# TimePassThrough.net
KiCad netlist of a schematic drawn in EAGLE
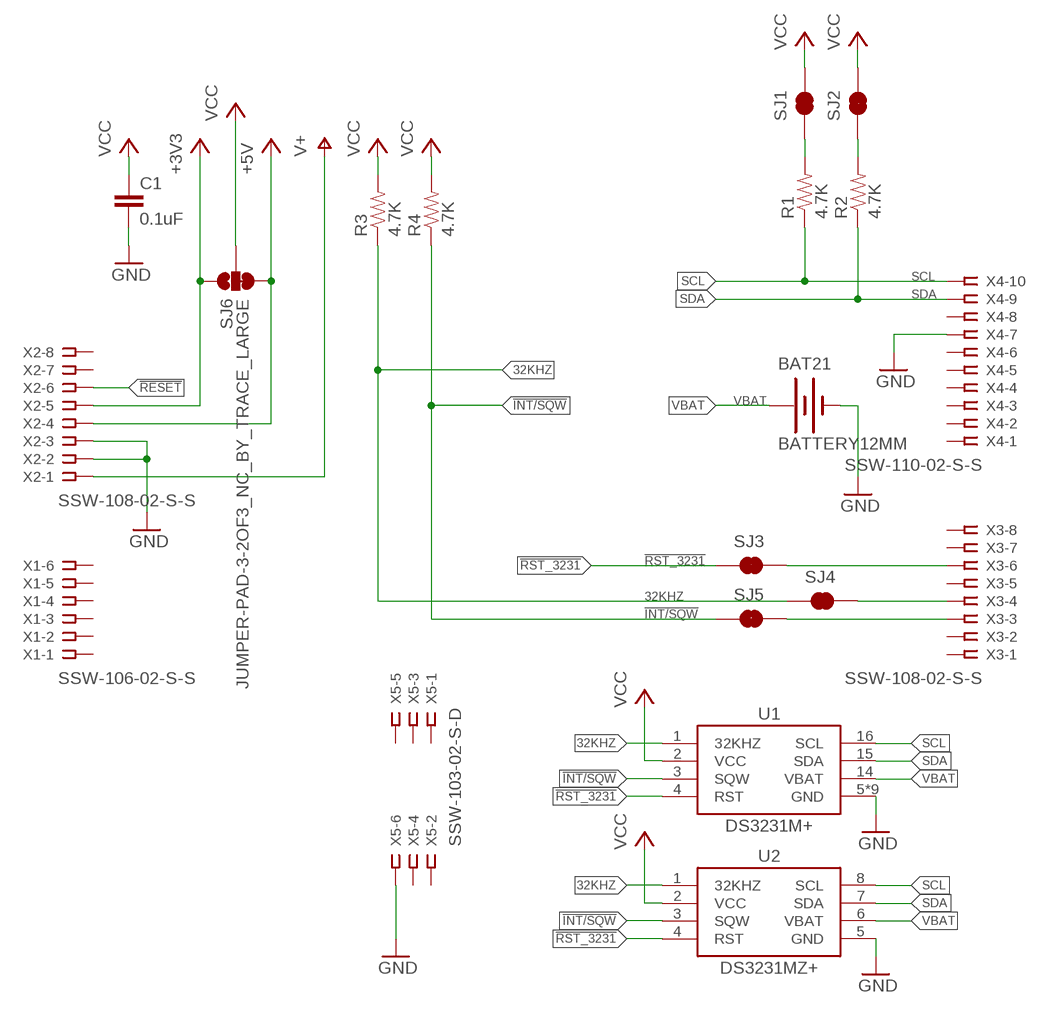
[diagram p0: schematic, sheet 1]

(export (version "E")
  (design (tool "Eeschema 10.0.6"))
  (components
    (comp (ref "BAT21")
      (value "BATTERY12MM")
      (footprint "eagle-import:BATTCON_12MM")
      (libsource (lib "eagle-import") (part "BATTERY12MM"))
    )
    (comp (ref "C1")
      (value "0.1uF")
      (footprint "eagle-import:0805")
      (libsource (lib "eagle-import") (part "CAP0805"))
    )
    (comp (ref "R1")
      (value "4.7K")
      (footprint "eagle-import:0805")
      (libsource (lib "eagle-import") (part "RESISTOR0805-RES"))
    )
    (comp (ref "R2")
      (value "4.7K")
      (footprint "eagle-import:0805")
      (libsource (lib "eagle-import") (part "RESISTOR0805-RES"))
    )
    (comp (ref "R3")
      (value "4.7K")
      (footprint "eagle-import:0805")
      (libsource (lib "eagle-import") (part "RESISTOR0805-RES"))
    )
    (comp (ref "R4")
      (value "4.7K")
      (footprint "eagle-import:0805")
      (libsource (lib "eagle-import") (part "RESISTOR0805-RES"))
    )
    (comp (ref "SJ1")
      (value "JUMPER-PAD-2-NC_BY_TRACE")
      (footprint "eagle-import:PAD-JUMPER-2-NC_BY_TRACE_YES_SILK")
      (libsource (lib "eagle-import") (part "JUMPER-PAD-2-NC_BY_TRACE"))
    )
    (comp (ref "SJ2")
      (value "JUMPER-PAD-2-NC_BY_TRACE")
      (footprint "eagle-import:PAD-JUMPER-2-NC_BY_TRACE_YES_SILK")
      (libsource (lib "eagle-import") (part "JUMPER-PAD-2-NC_BY_TRACE"))
    )
    (comp (ref "SJ3")
      (value "JUMPER-PAD-2-NC_BY_TRACE")
      (footprint "eagle-import:PAD-JUMPER-2-NC_BY_TRACE_YES_SILK")
      (libsource (lib "eagle-import") (part "JUMPER-PAD-2-NC_BY_TRACE"))
    )
    (comp (ref "SJ4")
      (value "JUMPER-PAD-2-NC_BY_TRACE")
      (footprint "eagle-import:PAD-JUMPER-2-NC_BY_TRACE_YES_SILK")
      (libsource (lib "eagle-import") (part "JUMPER-PAD-2-NC_BY_TRACE"))
    )
    (comp (ref "SJ5")
      (value "JUMPER-PAD-2-NC_BY_TRACE")
      (footprint "eagle-import:PAD-JUMPER-2-NC_BY_TRACE_YES_SILK")
      (libsource (lib "eagle-import") (part "JUMPER-PAD-2-NC_BY_TRACE"))
    )
    (comp (ref "SJ6")
      (value "JUMPER-PAD-3-2OF3_NC_BY_TRACE_LARGE")
      (footprint "eagle-import:PAD-JUMPER-3-2OF3_NC_BY_TRACE_YES_SILK_LARGE")
      (libsource (lib "eagle-import") (part "JUMPER-PAD-3-2OF3_NC_BY_TRACE_LARGE"))
    )
    (comp (ref "U1")
      (value "DS3231M+")
      (footprint "eagle-import:W16MK+1")
      (libsource (lib "eagle-import") (part "DS3231M+"))
    )
    (comp (ref "U2")
      (value "DS3231MZ+")
      (footprint "eagle-import:S8MK+1")
      (libsource (lib "eagle-import") (part "DS3231MZ+"))
    )
    (comp (ref "X1")
      (value "SSW-106-02-S-S")
      (footprint "eagle-import:SSW-106-02-S-S")
      (libsource (lib "eagle-import") (part "SSW-106-02-S-S"))
    )
    (comp (ref "X2")
      (value "SSW-108-02-S-S")
      (footprint "eagle-import:SSW-108-02-S-S")
      (libsource (lib "eagle-import") (part "SSW-108-02-S-S"))
    )
    (comp (ref "X3")
      (value "SSW-108-02-S-S")
      (footprint "eagle-import:SSW-108-02-S-S")
      (libsource (lib "eagle-import") (part "SSW-108-02-S-S"))
    )
    (comp (ref "X4")
      (value "SSW-110-02-S-S")
      (footprint "eagle-import:SSW-110-02-S-S")
      (libsource (lib "eagle-import") (part "SSW-110-02-S-S"))
    )
    (comp (ref "X5")
      (value "SSW-103-02-S-D")
      (footprint "eagle-import:SSW-103-02-S-D")
      (libsource (lib "eagle-import") (part "SSW-103-02-S-D"))
    )
  )
  (nets
    (net (code "1") (name "+3V3") (class "Default")
      (node (ref "SJ6") (pin "1") (pinfunction "1_1") (pintype "passive"))
      (node (ref "X2") (pin "5") (pinfunction "1_5") (pintype "passive"))
    )
    (net (code "2") (name "+5V") (class "Default")
      (node (ref "SJ6") (pin "3") (pinfunction "3_3") (pintype "passive"))
      (node (ref "X2") (pin "4") (pinfunction "1_4") (pintype "passive"))
    )
    (net (code "3") (name "/~{INT{slash}SQW}") (class "Default")
      (node (ref "R4") (pin "1") (pinfunction "1_1") (pintype "passive"))
      (node (ref "SJ5") (pin "1") (pinfunction "1_1") (pintype "passive"))
      (node (ref "U1") (pin "3") (pinfunction "SQW_3") (pintype "output"))
      (node (ref "U2") (pin "3") (pinfunction "SQW_3") (pintype "output"))
    )
    (net (code "4") (name "/~{RESET}") (class "Default")
      (node (ref "X2") (pin "6") (pinfunction "1_6") (pintype "passive"))
    )
    (net (code "5") (name "/~{RST_3231}") (class "Default")
      (node (ref "SJ3") (pin "1") (pinfunction "1_1") (pintype "passive"))
      (node (ref "U1") (pin "4") (pinfunction "RST_4") (pintype "bidirectional"))
      (node (ref "U2") (pin "4") (pinfunction "RST_4") (pintype "bidirectional"))
    )
    (net (code "6") (name "32KHZ") (class "Default")
      (node (ref "R3") (pin "1") (pinfunction "1_1") (pintype "passive"))
      (node (ref "SJ4") (pin "1") (pinfunction "1_1") (pintype "passive"))
      (node (ref "U1") (pin "1") (pinfunction "32KHZ_1") (pintype "output"))
      (node (ref "U2") (pin "1") (pinfunction "32KHZ_1") (pintype "output"))
    )
    (net (code "7") (name "GND") (class "Default")
      (node (ref "BAT21") (pin "GND") (pinfunction "-_GND") (pintype "passive"))
      (node (ref "C1") (pin "2") (pinfunction "2_2") (pintype "passive"))
      (node (ref "U1") (pin "10") (pinfunction "GND_10") (pintype "power_in"))
      (node (ref "U1") (pin "11") (pinfunction "GND_11") (pintype "power_in"))
      (node (ref "U1") (pin "12") (pinfunction "GND_12") (pintype "power_in"))
      (node (ref "U1") (pin "13") (pinfunction "GND_13") (pintype "power_in"))
      (node (ref "U1") (pin "5") (pinfunction "GND_5") (pintype "power_in"))
      (node (ref "U1") (pin "6") (pinfunction "GND_6") (pintype "power_in"))
      (node (ref "U1") (pin "7") (pinfunction "GND_7") (pintype "power_in"))
      (node (ref "U1") (pin "8") (pinfunction "GND_8") (pintype "power_in"))
      (node (ref "U1") (pin "9") (pinfunction "GND_9") (pintype "power_in"))
      (node (ref "U2") (pin "5") (pinfunction "GND_5") (pintype "power_in"))
      (node (ref "X2") (pin "2") (pinfunction "1_2") (pintype "passive"))
      (node (ref "X2") (pin "3") (pinfunction "1_3") (pintype "passive"))
      (node (ref "X4") (pin "7") (pinfunction "1_7") (pintype "passive"))
      (node (ref "X5") (pin "6") (pinfunction "1_6") (pintype "passive"))
    )
    (net (code "8") (name "Net-(R1-Pad2)") (class "Default")
      (node (ref "R1") (pin "2") (pinfunction "2_2") (pintype "passive"))
      (node (ref "SJ1") (pin "1") (pinfunction "1_1") (pintype "passive"))
    )
    (net (code "9") (name "Net-(R2-Pad2)") (class "Default")
      (node (ref "R2") (pin "2") (pinfunction "2_2") (pintype "passive"))
      (node (ref "SJ2") (pin "1") (pinfunction "1_1") (pintype "passive"))
    )
    (net (code "10") (name "Net-(X3C-1)") (class "Default")
      (node (ref "SJ5") (pin "2") (pinfunction "2_2") (pintype "passive"))
      (node (ref "X3") (pin "3") (pinfunction "1_3") (pintype "passive"))
    )
    (net (code "11") (name "Net-(X3D-1)") (class "Default")
      (node (ref "SJ4") (pin "2") (pinfunction "2_2") (pintype "passive"))
      (node (ref "X3") (pin "4") (pinfunction "1_4") (pintype "passive"))
    )
    (net (code "12") (name "Net-(X3F-1)") (class "Default")
      (node (ref "SJ3") (pin "2") (pinfunction "2_2") (pintype "passive"))
      (node (ref "X3") (pin "6") (pinfunction "1_6") (pintype "passive"))
    )
    (net (code "13") (name "SCL") (class "Default")
      (node (ref "R1") (pin "1") (pinfunction "1_1") (pintype "passive"))
      (node (ref "U1") (pin "16") (pinfunction "SCL_16") (pintype "bidirectional"))
      (node (ref "U2") (pin "8") (pinfunction "SCL_8") (pintype "bidirectional"))
      (node (ref "X4") (pin "10") (pinfunction "1_10") (pintype "passive"))
    )
    (net (code "14") (name "SDA") (class "Default")
      (node (ref "R2") (pin "1") (pinfunction "1_1") (pintype "passive"))
      (node (ref "U1") (pin "15") (pinfunction "SDA_15") (pintype "bidirectional"))
      (node (ref "U2") (pin "7") (pinfunction "SDA_7") (pintype "bidirectional"))
      (node (ref "X4") (pin "9") (pinfunction "1_9") (pintype "passive"))
    )
    (net (code "15") (name "V+") (class "Default")
      (node (ref "X2") (pin "1") (pinfunction "1_1") (pintype "passive"))
    )
    (net (code "16") (name "VBAT") (class "Default")
      (node (ref "BAT21") (pin "PWR@1") (pinfunction "+_PWR@1") (pintype "power_in"))
      (node (ref "BAT21") (pin "PWR@2") (pinfunction "+_PWR@2") (pintype "power_in"))
      (node (ref "U1") (pin "14") (pinfunction "VBAT_14") (pintype "power_in"))
      (node (ref "U2") (pin "6") (pinfunction "VBAT_6") (pintype "power_in"))
    )
    (net (code "17") (name "VCC") (class "Default")
      (node (ref "C1") (pin "1") (pinfunction "1_1") (pintype "passive"))
      (node (ref "R3") (pin "2") (pinfunction "2_2") (pintype "passive"))
      (node (ref "R4") (pin "2") (pinfunction "2_2") (pintype "passive"))
      (node (ref "SJ1") (pin "2") (pinfunction "2_2") (pintype "passive"))
      (node (ref "SJ2") (pin "2") (pinfunction "2_2") (pintype "passive"))
      (node (ref "SJ6") (pin "2") (pinfunction "2_2") (pintype "passive"))
      (node (ref "U1") (pin "2") (pinfunction "VCC_2") (pintype "power_in"))
      (node (ref "U2") (pin "2") (pinfunction "VCC_2") (pintype "power_in"))
    )
    (net (code "18") (name "unconnected-(X1-Pad1)") (class "Default")
      (node (ref "X1") (pin "1") (pinfunction "1_1") (pintype "passive"))
    )
    (net (code "19") (name "unconnected-(X1B-1-Pad2)") (class "Default")
      (node (ref "X1") (pin "2") (pinfunction "1_2") (pintype "passive"))
    )
    (net (code "20") (name "unconnected-(X1C-1-Pad3)") (class "Default")
      (node (ref "X1") (pin "3") (pinfunction "1_3") (pintype "passive"))
    )
    (net (code "21") (name "unconnected-(X1D-1-Pad4)") (class "Default")
      (node (ref "X1") (pin "4") (pinfunction "1_4") (pintype "passive"))
    )
    (net (code "22") (name "unconnected-(X1E-1-Pad5)") (class "Default")
      (node (ref "X1") (pin "5") (pinfunction "1_5") (pintype "passive"))
    )
    (net (code "23") (name "unconnected-(X1F-1-Pad6)") (class "Default")
      (node (ref "X1") (pin "6") (pinfunction "1_6") (pintype "passive"))
    )
    (net (code "24") (name "unconnected-(X2G-1-Pad7)") (class "Default")
      (node (ref "X2") (pin "7") (pinfunction "1_7") (pintype "passive"))
    )
    (net (code "25") (name "unconnected-(X2H-1-Pad8)") (class "Default")
      (node (ref "X2") (pin "8") (pinfunction "1_8") (pintype "passive"))
    )
    (net (code "26") (name "unconnected-(X3-Pad1)") (class "Default")
      (node (ref "X3") (pin "1") (pinfunction "1_1") (pintype "passive"))
    )
    (net (code "27") (name "unconnected-(X3B-1-Pad2)") (class "Default")
      (node (ref "X3") (pin "2") (pinfunction "1_2") (pintype "passive"))
    )
    (net (code "28") (name "unconnected-(X3E-1-Pad5)") (class "Default")
      (node (ref "X3") (pin "5") (pinfunction "1_5") (pintype "passive"))
    )
    (net (code "29") (name "unconnected-(X3G-1-Pad7)") (class "Default")
      (node (ref "X3") (pin "7") (pinfunction "1_7") (pintype "passive"))
    )
    (net (code "30") (name "unconnected-(X3H-1-Pad8)") (class "Default")
      (node (ref "X3") (pin "8") (pinfunction "1_8") (pintype "passive"))
    )
    (net (code "31") (name "unconnected-(X4-Pad1)") (class "Default")
      (node (ref "X4") (pin "1") (pinfunction "1_1") (pintype "passive"))
    )
    (net (code "32") (name "unconnected-(X4C-1-Pad2)") (class "Default")
      (node (ref "X4") (pin "2") (pinfunction "1_2") (pintype "passive"))
    )
    (net (code "33") (name "unconnected-(X4D-1-Pad3)") (class "Default")
      (node (ref "X4") (pin "3") (pinfunction "1_3") (pintype "passive"))
    )
    (net (code "34") (name "unconnected-(X4E-1-Pad4)") (class "Default")
      (node (ref "X4") (pin "4") (pinfunction "1_4") (pintype "passive"))
    )
    (net (code "35") (name "unconnected-(X4F-1-Pad5)") (class "Default")
      (node (ref "X4") (pin "5") (pinfunction "1_5") (pintype "passive"))
    )
    (net (code "36") (name "unconnected-(X4G-1-Pad6)") (class "Default")
      (node (ref "X4") (pin "6") (pinfunction "1_6") (pintype "passive"))
    )
    (net (code "37") (name "unconnected-(X4I-1-Pad8)") (class "Default")
      (node (ref "X4") (pin "8") (pinfunction "1_8") (pintype "passive"))
    )
    (net (code "38") (name "unconnected-(X5-Pad1)") (class "Default")
      (node (ref "X5") (pin "1") (pinfunction "1_1") (pintype "passive"))
    )
    (net (code "39") (name "unconnected-(X5B-1-Pad2)") (class "Default")
      (node (ref "X5") (pin "2") (pinfunction "1_2") (pintype "passive"))
    )
    (net (code "40") (name "unconnected-(X5C-1-Pad3)") (class "Default")
      (node (ref "X5") (pin "3") (pinfunction "1_3") (pintype "passive"))
    )
    (net (code "41") (name "unconnected-(X5D-1-Pad4)") (class "Default")
      (node (ref "X5") (pin "4") (pinfunction "1_4") (pintype "passive"))
    )
    (net (code "42") (name "unconnected-(X5E-1-Pad5)") (class "Default")
      (node (ref "X5") (pin "5") (pinfunction "1_5") (pintype "passive"))
    )
  )
)
